# Indicate.net
KiCad netlist of a schematic drawn in Altium Designer
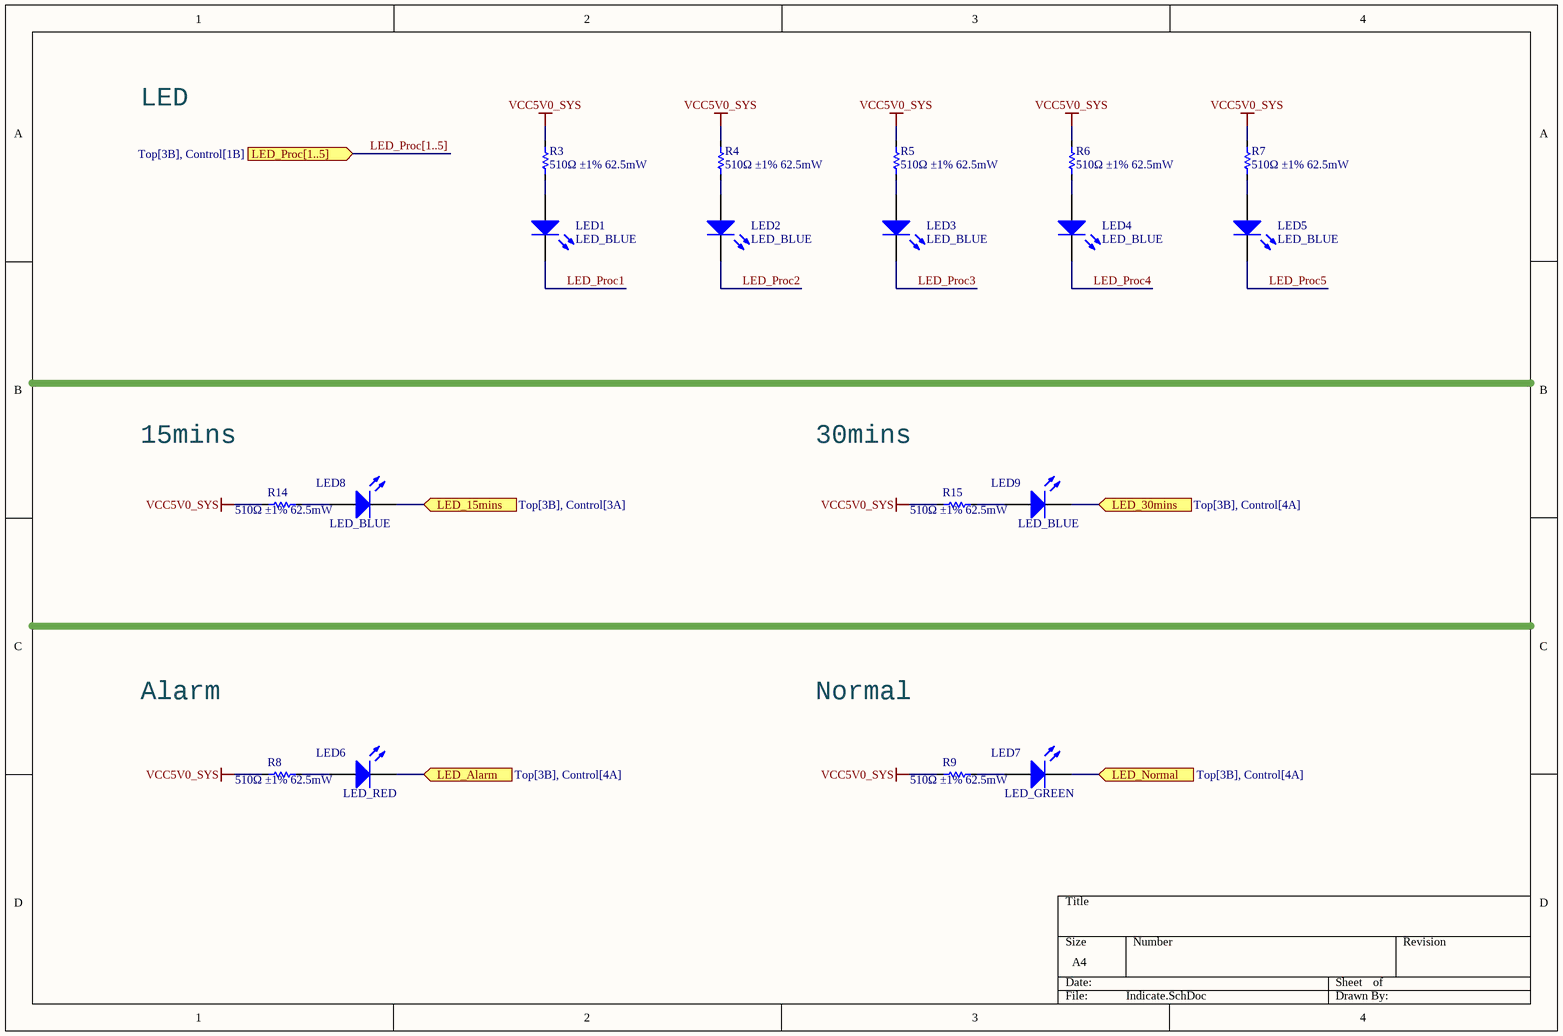
[diagram p0: Indicate.SchDoc]

(export (version "E")
  (design (tool "Eeschema 10.0.6"))
  (components
    (comp (ref "LED1")
      (value "LED_BLUE")
      (footprint "LED0603")
      (description "XL-1608UBC-04")
      (fields (field (name "PUBLISHER") "Altium Limited"))
      (libsource (lib "Miscellaneous Devices") (part "LED2"))
    )
    (comp (ref "LED2")
      (value "LED_BLUE")
      (footprint "LED0603")
      (description "XL-1608UBC-04")
      (fields (field (name "PUBLISHER") "Altium Limited"))
      (libsource (lib "Miscellaneous Devices") (part "LED2"))
    )
    (comp (ref "LED3")
      (value "LED_BLUE")
      (footprint "LED0603")
      (description "XL-1608UBC-04")
      (fields (field (name "PUBLISHER") "Altium Limited"))
      (libsource (lib "Miscellaneous Devices") (part "LED2"))
    )
    (comp (ref "LED4")
      (value "LED_BLUE")
      (footprint "LED0603")
      (description "XL-1608UBC-04")
      (fields (field (name "PUBLISHER") "Altium Limited"))
      (libsource (lib "Miscellaneous Devices") (part "LED2"))
    )
    (comp (ref "LED5")
      (value "LED_BLUE")
      (footprint "LED0603")
      (description "XL-1608UBC-04")
      (fields (field (name "PUBLISHER") "Altium Limited"))
      (libsource (lib "Miscellaneous Devices") (part "LED2"))
    )
    (comp (ref "LED6")
      (value "LED_RED")
      (footprint "LED0603")
      (description "XL-1608SURC-06")
      (fields (field (name "PUBLISHER") "Altium Limited"))
      (libsource (lib "Miscellaneous Devices") (part "LED2"))
    )
    (comp (ref "LED7")
      (value "LED_GREEN")
      (footprint "LED0603")
      (description "XL-1608PGC-06")
      (fields (field (name "PUBLISHER") "Altium Limited"))
      (libsource (lib "Miscellaneous Devices") (part "LED2"))
    )
    (comp (ref "LED8")
      (value "LED_BLUE")
      (footprint "LED0603")
      (description "XL-1608UBC-04")
      (fields (field (name "PUBLISHER") "Altium Limited"))
      (libsource (lib "Miscellaneous Devices") (part "LED2"))
    )
    (comp (ref "LED9")
      (value "LED_BLUE")
      (footprint "LED0603")
      (description "XL-1608UBC-04")
      (fields (field (name "PUBLISHER") "Altium Limited"))
      (libsource (lib "Miscellaneous Devices") (part "LED2"))
    )
    (comp (ref "R3")
      (value "510Ω ±1% 62.5mW")
      (footprint "R0402")
      (description "0402WGF5100TCE")
      (fields (field (name "PUBLISHER") "Altium Limited"))
      (libsource (lib "Component") (part "R0402"))
    )
    (comp (ref "R4")
      (value "510Ω ±1% 62.5mW")
      (footprint "R0402")
      (description "0402WGF5100TCE")
      (fields (field (name "PUBLISHER") "Altium Limited"))
      (libsource (lib "Component") (part "R0402"))
    )
    (comp (ref "R5")
      (value "510Ω ±1% 62.5mW")
      (footprint "R0402")
      (description "0402WGF5100TCE")
      (fields (field (name "PUBLISHER") "Altium Limited"))
      (libsource (lib "Component") (part "R0402"))
    )
    (comp (ref "R6")
      (value "510Ω ±1% 62.5mW")
      (footprint "R0402")
      (description "0402WGF5100TCE")
      (fields (field (name "PUBLISHER") "Altium Limited"))
      (libsource (lib "Component") (part "R0402"))
    )
    (comp (ref "R7")
      (value "510Ω ±1% 62.5mW")
      (footprint "R0402")
      (description "0402WGF5100TCE")
      (fields (field (name "PUBLISHER") "Altium Limited"))
      (libsource (lib "Component") (part "R0402"))
    )
    (comp (ref "R8")
      (value "510Ω ±1% 62.5mW")
      (footprint "R0402")
      (description "0402WGF5100TCE")
      (fields (field (name "PUBLISHER") "Altium Limited"))
      (libsource (lib "Component") (part "R0402"))
    )
    (comp (ref "R9")
      (value "510Ω ±1% 62.5mW")
      (footprint "R0402")
      (description "0402WGF5100TCE")
      (fields (field (name "PUBLISHER") "Altium Limited"))
      (libsource (lib "Component") (part "R0402"))
    )
    (comp (ref "R14")
      (value "510Ω ±1% 62.5mW")
      (footprint "R0402")
      (description "0402WGF5100TCE")
      (fields (field (name "PUBLISHER") "Altium Limited"))
      (libsource (lib "Component") (part "R0402"))
    )
    (comp (ref "R15")
      (value "510Ω ±1% 62.5mW")
      (footprint "R0402")
      (description "0402WGF5100TCE")
      (fields (field (name "PUBLISHER") "Altium Limited"))
      (libsource (lib "Component") (part "R0402"))
    )
  )
  (nets
    (net (code "1") (name "/LED_15mins") (class "Default")
      (node (ref "LED8") (pin "2") (pinfunction "K_2") (pintype "passive"))
    )
    (net (code "2") (name "/LED_30mins") (class "Default")
      (node (ref "LED9") (pin "2") (pinfunction "K_2") (pintype "passive"))
    )
    (net (code "3") (name "/LED_Alarm") (class "Default")
      (node (ref "LED6") (pin "2") (pinfunction "K_2") (pintype "passive"))
    )
    (net (code "4") (name "/LED_Normal") (class "Default")
      (node (ref "LED7") (pin "2") (pinfunction "K_2") (pintype "passive"))
    )
    (net (code "5") (name "/LED_Proc1") (class "Default")
      (node (ref "LED1") (pin "2") (pinfunction "K_2") (pintype "passive"))
    )
    (net (code "6") (name "/LED_Proc2") (class "Default")
      (node (ref "LED2") (pin "2") (pinfunction "K_2") (pintype "passive"))
    )
    (net (code "7") (name "/LED_Proc3") (class "Default")
      (node (ref "LED3") (pin "2") (pinfunction "K_2") (pintype "passive"))
    )
    (net (code "8") (name "/LED_Proc4") (class "Default")
      (node (ref "LED4") (pin "2") (pinfunction "K_2") (pintype "passive"))
    )
    (net (code "9") (name "/LED_Proc5") (class "Default")
      (node (ref "LED5") (pin "2") (pinfunction "K_2") (pintype "passive"))
    )
    (net (code "11") (name "Net-(LED1-A)") (class "Default")
      (node (ref "LED1") (pin "1") (pinfunction "A_1") (pintype "passive"))
      (node (ref "R3") (pin "1") (pinfunction "1_1") (pintype "passive"))
    )
    (net (code "12") (name "Net-(LED2-A)") (class "Default")
      (node (ref "LED2") (pin "1") (pinfunction "A_1") (pintype "passive"))
      (node (ref "R4") (pin "1") (pinfunction "1_1") (pintype "passive"))
    )
    (net (code "13") (name "Net-(LED3-A)") (class "Default")
      (node (ref "LED3") (pin "1") (pinfunction "A_1") (pintype "passive"))
      (node (ref "R5") (pin "1") (pinfunction "1_1") (pintype "passive"))
    )
    (net (code "14") (name "Net-(LED4-A)") (class "Default")
      (node (ref "LED4") (pin "1") (pinfunction "A_1") (pintype "passive"))
      (node (ref "R6") (pin "1") (pinfunction "1_1") (pintype "passive"))
    )
    (net (code "15") (name "Net-(LED5-A)") (class "Default")
      (node (ref "LED5") (pin "1") (pinfunction "A_1") (pintype "passive"))
      (node (ref "R7") (pin "1") (pinfunction "1_1") (pintype "passive"))
    )
    (net (code "16") (name "Net-(LED6-A)") (class "Default")
      (node (ref "LED6") (pin "1") (pinfunction "A_1") (pintype "passive"))
      (node (ref "R8") (pin "2") (pinfunction "2_2") (pintype "passive"))
    )
    (net (code "17") (name "Net-(LED7-A)") (class "Default")
      (node (ref "LED7") (pin "1") (pinfunction "A_1") (pintype "passive"))
      (node (ref "R9") (pin "2") (pinfunction "2_2") (pintype "passive"))
    )
    (net (code "18") (name "Net-(LED8-A)") (class "Default")
      (node (ref "LED8") (pin "1") (pinfunction "A_1") (pintype "passive"))
      (node (ref "R14") (pin "2") (pinfunction "2_2") (pintype "passive"))
    )
    (net (code "19") (name "Net-(LED9-A)") (class "Default")
      (node (ref "LED9") (pin "1") (pinfunction "A_1") (pintype "passive"))
      (node (ref "R15") (pin "2") (pinfunction "2_2") (pintype "passive"))
    )
    (net (code "20") (name "VCC5V0_SYS") (class "Default")
      (node (ref "R14") (pin "1") (pinfunction "1_1") (pintype "passive"))
      (node (ref "R15") (pin "1") (pinfunction "1_1") (pintype "passive"))
      (node (ref "R3") (pin "2") (pinfunction "2_2") (pintype "passive"))
      (node (ref "R4") (pin "2") (pinfunction "2_2") (pintype "passive"))
      (node (ref "R5") (pin "2") (pinfunction "2_2") (pintype "passive"))
      (node (ref "R6") (pin "2") (pinfunction "2_2") (pintype "passive"))
      (node (ref "R7") (pin "2") (pinfunction "2_2") (pintype "passive"))
      (node (ref "R8") (pin "1") (pinfunction "1_1") (pintype "passive"))
      (node (ref "R9") (pin "1") (pinfunction "1_1") (pintype "passive"))
    )
  )
)
